# ISL6236A_DEMO.net
KiCad netlist of a schematic drawn in Altium Designer
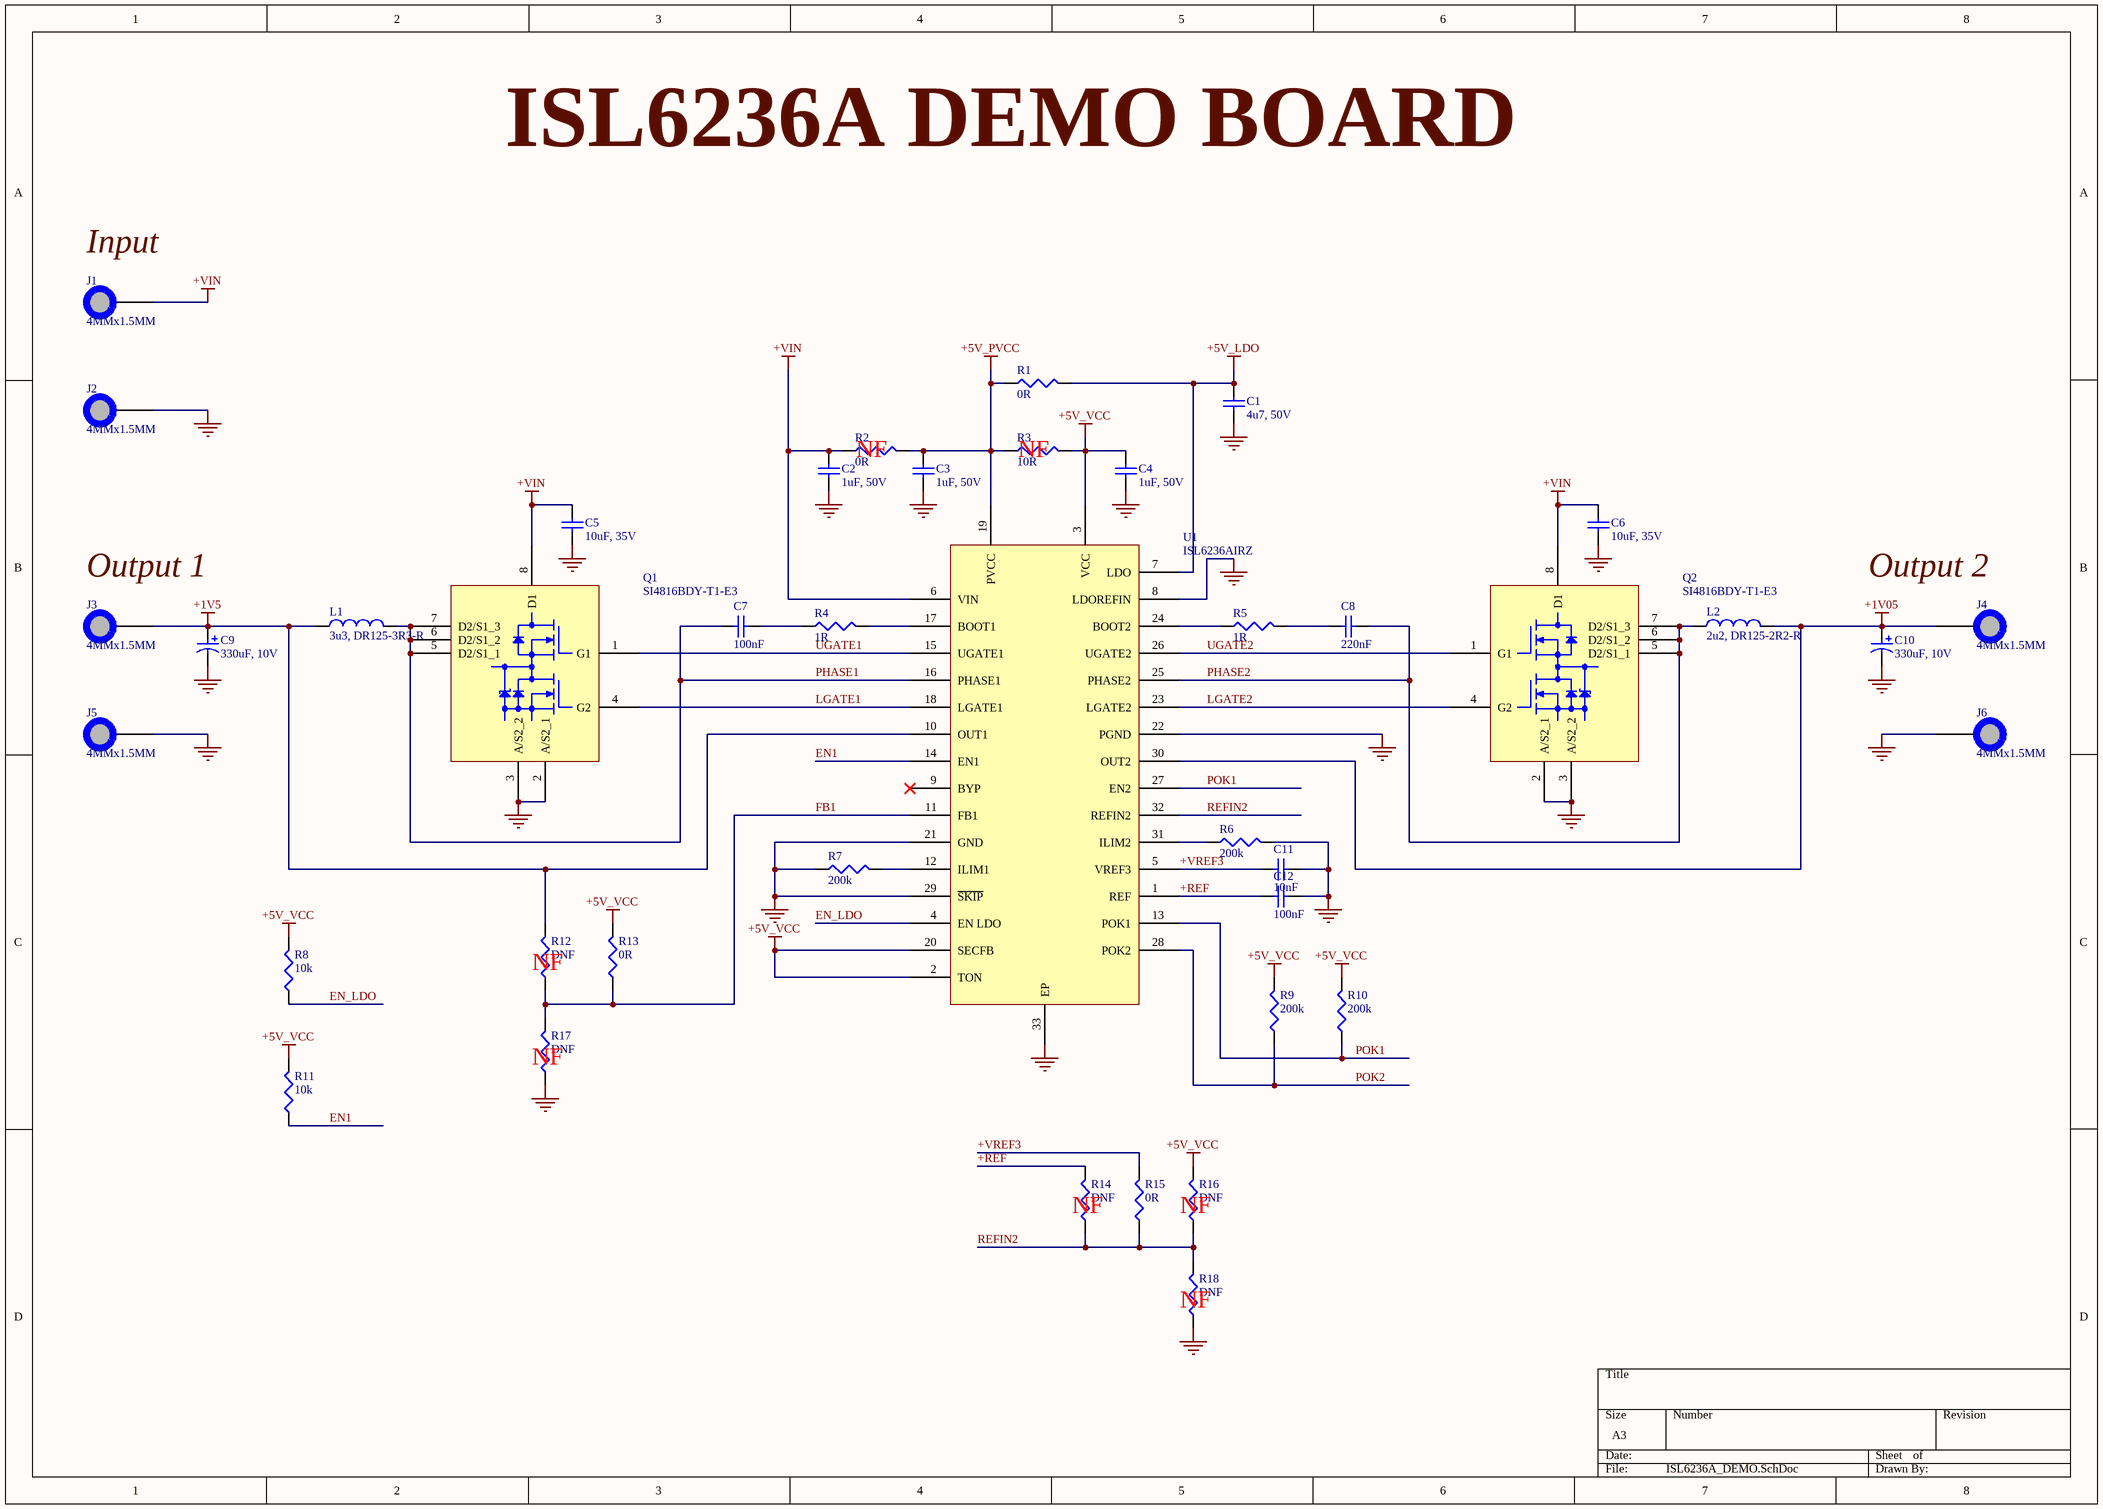
[diagram p0: ISL6236A_DEMO.SchDoc]

(export (version "E")
  (design (tool "Eeschema 10.0.6"))
  (components
    (comp (ref "C1")
      (value "4u7, 50V")
      (footprint "C1206")
      (description "CAP CER 4.7UF 50V X5R 1206")
      (fields
        (field (name "MANUFACTURER") "TDK")
        (field (name "MANUFACTURER PART NUMBER") "C3216X5R1H475K160AB")
      )
      (libsource (lib "ISL6236A_DEMO") (part "C3216X5R1H475K160AB"))
    )
    (comp (ref "C2")
      (value "1uF, 50V")
      (footprint "C0805")
      (description "Multilayer Ceramic Capacitors MLCC - SMD/SMT 1uF 50 Volts 10% X7R")
      (fields
        (field (name "MANUFACTURER") "KEMET")
        (field (name "MANUFACTURER PART NUMBER") "C0805C105K5RACTU")
      )
      (libsource (lib "ISL6236A_DEMO") (part "C0805C105K5RACTU"))
    )
    (comp (ref "C3")
      (value "1uF, 50V")
      (footprint "C0805")
      (description "Multilayer Ceramic Capacitors MLCC - SMD/SMT 1uF 50 Volts 10% X7R")
      (fields
        (field (name "MANUFACTURER") "KEMET")
        (field (name "MANUFACTURER PART NUMBER") "C0805C105K5RACTU")
      )
      (libsource (lib "ISL6236A_DEMO") (part "C0805C105K5RACTU"))
    )
    (comp (ref "C4")
      (value "1uF, 50V")
      (footprint "C0805")
      (description "Multilayer Ceramic Capacitors MLCC - SMD/SMT 1uF 50 Volts 10% X7R")
      (fields
        (field (name "MANUFACTURER") "KEMET")
        (field (name "MANUFACTURER PART NUMBER") "C0805C105K5RACTU")
      )
      (libsource (lib "ISL6236A_DEMO") (part "C0805C105K5RACTU"))
    )
    (comp (ref "C5")
      (value "10uF, 35V")
      (footprint "C1210")
      (description "1210 C 10uF Ceramic Multilayer Capacitor,  35 VDC,  +85degC,  X5R Dielec,  +/-10%")
      (fields
        (field (name "MANUFACTURER") "KEMET")
        (field (name "MANUFACTURER PART NUMBER") "C1210C106K6PACTU")
      )
      (libsource (lib "ISL6236A_DEMO") (part "C1210C106K6PACTU"))
    )
    (comp (ref "C6")
      (value "10uF, 35V")
      (footprint "C1210")
      (description "1210 C 10uF Ceramic Multilayer Capacitor,  35 VDC,  +85degC,  X5R Dielec,  +/-10%")
      (fields
        (field (name "MANUFACTURER") "KEMET")
        (field (name "MANUFACTURER PART NUMBER") "C1210C106K6PACTU")
      )
      (libsource (lib "ISL6236A_DEMO") (part "C1210C106K6PACTU"))
    )
    (comp (ref "C7")
      (value "100nF")
      (footprint "C0805")
      (description "Multilayer Ceramic Capacitors MLCC - SMD/SMT 50volts 0.1uF X7R 10%")
      (fields
        (field (name "MANUFACTURER") "KEMET")
        (field (name "MANUFACTURER PART NUMBER") "C0805C104K5RAC7800")
      )
      (libsource (lib "ISL6236A_DEMO") (part "C0805C104K5RAC7800"))
    )
    (comp (ref "C8")
      (value "220nF")
      (footprint "C0805")
      (description "CAP CER 0.22UF 50V X7R 0805")
      (fields
        (field (name "MANUFACTURER") "KEMET")
        (field (name "MANUFACTURER PART NUMBER") "C0805C224K5RACTU")
      )
      (libsource (lib "ISL6236A_DEMO") (part "C0805C224K5RACTU"))
    )
    (comp (ref "C9")
      (value "330uF, 10V")
      (footprint "7343-43")
      (description "Tantalum Capacitors - Polymer SMD 330uF 10volts 20%")
      (fields
        (field (name "MANUFACTURER") "KEMET")
        (field (name "MANUFACTURER PART NUMBER") "T530X337M010ATE004")
      )
      (libsource (lib "ISL6236A_DEMO") (part "T530X337M010ATE004"))
    )
    (comp (ref "C10")
      (value "330uF, 10V")
      (footprint "7343-43")
      (description "Tantalum Capacitors - Polymer SMD 330uF 10volts 20%")
      (fields
        (field (name "MANUFACTURER") "KEMET")
        (field (name "MANUFACTURER PART NUMBER") "T530X337M010ATE004")
      )
      (libsource (lib "ISL6236A_DEMO") (part "T530X337M010ATE004"))
    )
    (comp (ref "C11")
      (value "10nF")
      (footprint "C0805")
      (description "CAP CER 10000PF 50V X7R 0805")
      (fields
        (field (name "MANUFACTURER") "KEMET")
        (field (name "MANUFACTURER PART NUMBER") "C0805F103K5RACTU")
      )
      (libsource (lib "ISL6236A_DEMO") (part "C0805F103K5RACTU"))
    )
    (comp (ref "C12")
      (value "100nF")
      (footprint "C0805")
      (description "Multilayer Ceramic Capacitors MLCC - SMD/SMT 50volts 0.1uF X7R 10%")
      (fields
        (field (name "MANUFACTURER") "KEMET")
        (field (name "MANUFACTURER PART NUMBER") "C0805C104K5RAC7800")
      )
      (libsource (lib "ISL6236A_DEMO") (part "C0805C104K5RAC7800"))
    )
    (comp (ref "J1")
      (value "4MMx1.5MM")
      (footprint "PAD_WITH_HOLE_4MMx1MM5")
      (description "Pad with a hole 4mm x 1.5mm")
      (libsource (lib "ISL6236A_DEMO") (part "PAD_WITH_HOLE_4MMx1MM5"))
    )
    (comp (ref "J2")
      (value "4MMx1.5MM")
      (footprint "PAD_WITH_HOLE_4MMx1MM5")
      (description "Pad with a hole 4mm x 1.5mm")
      (libsource (lib "ISL6236A_DEMO") (part "PAD_WITH_HOLE_4MMx1MM5"))
    )
    (comp (ref "J3")
      (value "4MMx1.5MM")
      (footprint "PAD_WITH_HOLE_4MMx1MM5")
      (description "Pad with a hole 4mm x 1.5mm")
      (libsource (lib "ISL6236A_DEMO") (part "PAD_WITH_HOLE_4MMx1MM5"))
    )
    (comp (ref "J4")
      (value "4MMx1.5MM")
      (footprint "PAD_WITH_HOLE_4MMx1MM5")
      (description "Pad with a hole 4mm x 1.5mm")
      (libsource (lib "ISL6236A_DEMO") (part "PAD_WITH_HOLE_4MMx1MM5"))
    )
    (comp (ref "J5")
      (value "4MMx1.5MM")
      (footprint "PAD_WITH_HOLE_4MMx1MM5")
      (description "Pad with a hole 4mm x 1.5mm")
      (libsource (lib "ISL6236A_DEMO") (part "PAD_WITH_HOLE_4MMx1MM5"))
    )
    (comp (ref "J6")
      (value "4MMx1.5MM")
      (footprint "PAD_WITH_HOLE_4MMx1MM5")
      (description "Pad with a hole 4mm x 1.5mm")
      (libsource (lib "ISL6236A_DEMO") (part "PAD_WITH_HOLE_4MMx1MM5"))
    )
    (comp (ref "L1")
      (value "3u3, DR125-3R3-R")
      (footprint "DR125")
      (description "Inductor Power Shielded Drum Core 3.084uH/3.3uH 20% 100KHz Ferrite 9.26A 6.3mOhm DCR T/R")
      (fields
        (field (name "MANUFACTURER") "Eaton Cooper")
        (field (name "MANUFACTURER PART NUMBER") "DR125-3R3-R")
      )
      (libsource (lib "ISL6236A_DEMO") (part "DR125-3R3-R"))
    )
    (comp (ref "L2")
      (value "2u2, DR125-2R2-R")
      (footprint "DR125")
      (description "Fixed Inductors 2.2uH 15A 0.0045ohms")
      (fields
        (field (name "MANUFACTURER") "Eaton Cooper")
        (field (name "MANUFACTURER PART NUMBER") "DR125-2R2-R")
      )
      (libsource (lib "ISL6236A_DEMO") (part "DR125-2R2-R"))
    )
    (comp (ref "Q1")
      (value "SI4816BDY-T1-E3")
      (footprint "SO-8")
      (description "MOSFET 2N-CH 30V 5.8A 8-SOIC")
      (fields (field (name "MANUFACTURER") "Vishay Siliconix"))
      (libsource (lib "") (part "SI4816BDY-T1-E3_1"))
    )
    (comp (ref "Q2")
      (value "SI4816BDY-T1-E3")
      (footprint "SO-8")
      (description "MOSFET 2N-CH 30V 5.8A 8-SOIC")
      (fields (field (name "MANUFACTURER") "Vishay Siliconix"))
      (libsource (lib "ISL6236A_DEMO") (part "SI4816BDY-T1-E3"))
    )
    (comp (ref "R1")
      (value "0R")
      (footprint "R0805")
      (description "Thick Film Resistors - SMD 1/8W 0.0ohm 5%")
      (fields
        (field (name "MANUFACTURER") "Yageo")
        (field (name "MANUFACTURER PART NUMBER") "AC0805JR-070RL")
      )
      (libsource (lib "ISL6236A_DEMO") (part "AC0805JR-070RL"))
    )
    (comp (ref "R2")
      (value "0R")
      (footprint "R0805")
      (description "Thick Film Resistors - SMD 1/8W 0.0ohm 5%")
      (fields
        (field (name "MANUFACTURER") "Yageo")
        (field (name "MANUFACTURER PART NUMBER") "AC0805JR-070RL")
      )
      (libsource (lib "ISL6236A_DEMO") (part "AC0805JR-070RL"))
    )
    (comp (ref "R3")
      (value "10R")
      (footprint "R0805")
      (description "Thick Film Resistors - SMD 1/8W 10ohm 1%")
      (fields
        (field (name "MANUFACTURER") "Yageo")
        (field (name "MANUFACTURER PART NUMBER") "AC0805FR-0710RL")
      )
      (libsource (lib "ISL6236A_DEMO") (part "AC0805FR-0710RL"))
    )
    (comp (ref "R4")
      (value "1R")
      (footprint "R0805")
      (description "Thick Film Resistors - SMD 1/8W 1ohm 1% AEC-Q200")
      (fields
        (field (name "MANUFACTURER") "Yageo")
        (field (name "MANUFACTURER PART NUMBER") "AC0805FR-071RL")
      )
      (libsource (lib "ISL6236A_DEMO") (part "AC0805FR-071RL"))
    )
    (comp (ref "R5")
      (value "1R")
      (footprint "R0805")
      (description "Thick Film Resistors - SMD 1/8W 1ohm 1% AEC-Q200")
      (fields
        (field (name "MANUFACTURER") "Yageo")
        (field (name "MANUFACTURER PART NUMBER") "AC0805FR-071RL")
      )
      (libsource (lib "ISL6236A_DEMO") (part "AC0805FR-071RL"))
    )
    (comp (ref "R6")
      (value "200k")
      (footprint "R0805")
      (description "Thick Film Resistors - SMD 1/8W 200K ohm 1%")
      (fields
        (field (name "MANUFACTURER") "Yageo")
        (field (name "MANUFACTURER PART NUMBER") "AC0805FR-07200KL")
      )
      (libsource (lib "ISL6236A_DEMO") (part "AC0805FR-07200KL"))
    )
    (comp (ref "R7")
      (value "200k")
      (footprint "R0805")
      (description "Thick Film Resistors - SMD 1/8W 200K ohm 1%")
      (fields
        (field (name "MANUFACTURER") "Yageo")
        (field (name "MANUFACTURER PART NUMBER") "AC0805FR-07200KL")
      )
      (libsource (lib "ISL6236A_DEMO") (part "AC0805FR-07200KL"))
    )
    (comp (ref "R8")
      (value "10k")
      (footprint "R0805")
      (description "RES SMD 10K OHM 1% 1/8W 0805")
      (fields
        (field (name "MANUFACTURER") "Yageo")
        (field (name "MANUFACTURER PART NUMBER") "AC0805FR-0710KL")
      )
      (libsource (lib "ISL6236A_DEMO") (part "AC0805FR-0710KL"))
    )
    (comp (ref "R9")
      (value "200k")
      (footprint "R0805")
      (description "Thick Film Resistors - SMD 1/8W 200K ohm 1%")
      (fields
        (field (name "MANUFACTURER") "Yageo")
        (field (name "MANUFACTURER PART NUMBER") "AC0805FR-07200KL")
      )
      (libsource (lib "ISL6236A_DEMO") (part "AC0805FR-07200KL"))
    )
    (comp (ref "R10")
      (value "200k")
      (footprint "R0805")
      (description "Thick Film Resistors - SMD 1/8W 200K ohm 1%")
      (fields
        (field (name "MANUFACTURER") "Yageo")
        (field (name "MANUFACTURER PART NUMBER") "AC0805FR-07200KL")
      )
      (libsource (lib "ISL6236A_DEMO") (part "AC0805FR-07200KL"))
    )
    (comp (ref "R11")
      (value "10k")
      (footprint "R0805")
      (description "RES SMD 10K OHM 1% 1/8W 0805")
      (fields
        (field (name "MANUFACTURER") "Yageo")
        (field (name "MANUFACTURER PART NUMBER") "AC0805FR-0710KL")
      )
      (libsource (lib "ISL6236A_DEMO") (part "AC0805FR-0710KL"))
    )
    (comp (ref "R12") (value "DNF") (footprint "R0805") (libsource (lib "ISL6236A_DEMO") (part "RES")))
    (comp (ref "R13")
      (value "0R")
      (footprint "R0805")
      (description "Thick Film Resistors - SMD 1/8W 0.0ohm 5%")
      (fields
        (field (name "MANUFACTURER") "Yageo")
        (field (name "MANUFACTURER PART NUMBER") "AC0805JR-070RL")
      )
      (libsource (lib "ISL6236A_DEMO") (part "AC0805JR-070RL"))
    )
    (comp (ref "R14") (value "DNF") (footprint "R0805") (libsource (lib "ISL6236A_DEMO") (part "RES")))
    (comp (ref "R15")
      (value "0R")
      (footprint "R0805")
      (description "Thick Film Resistors - SMD 1/8W 0.0ohm 5%")
      (fields
        (field (name "MANUFACTURER") "Yageo")
        (field (name "MANUFACTURER PART NUMBER") "AC0805JR-070RL")
      )
      (libsource (lib "ISL6236A_DEMO") (part "AC0805JR-070RL"))
    )
    (comp (ref "R16") (value "DNF") (footprint "R0805") (libsource (lib "ISL6236A_DEMO") (part "RES")))
    (comp (ref "R17") (value "DNF") (footprint "R0805") (libsource (lib "ISL6236A_DEMO") (part "RES")))
    (comp (ref "R18") (value "DNF") (footprint "R0805") (libsource (lib "ISL6236A_DEMO") (part "RES")))
    (comp (ref "U1")
      (value "ISL6236AIRZ")
      (footprint "L32.5x5B")
      (description "IC MAIN PWR CTRLR QUAD 32-QFN")
      (fields (field (name "MANUFACTURER") "Intersil"))
      (libsource (lib "ISL6236A_DEMO") (part "ISL6236AIRZ"))
    )
  )
  (nets
    (net (code "1") (name "+1V05") (class "Default")
      (node (ref "C10") (pin "1") (pinfunction "1_1") (pintype "passive"))
      (node (ref "J4") (pin "1") (pinfunction "1_1") (pintype "passive"))
      (node (ref "L2") (pin "2") (pinfunction "2_2") (pintype "passive"))
      (node (ref "U1") (pin "30") (pinfunction "OUT2_30") (pintype "passive"))
    )
    (net (code "2") (name "+1V5") (class "Default")
      (node (ref "C9") (pin "1") (pinfunction "1_1") (pintype "passive"))
      (node (ref "J3") (pin "1") (pinfunction "1_1") (pintype "passive"))
      (node (ref "L1") (pin "1") (pinfunction "1_1") (pintype "passive"))
      (node (ref "R12") (pin "2") (pinfunction "2_2") (pintype "passive"))
      (node (ref "U1") (pin "10") (pinfunction "OUT1_10") (pintype "passive"))
    )
    (net (code "3") (name "+5V_LDO") (class "Default")
      (node (ref "C1") (pin "2") (pinfunction "2_2") (pintype "passive"))
      (node (ref "R1") (pin "2") (pinfunction "2_2") (pintype "passive"))
      (node (ref "U1") (pin "7") (pinfunction "LDO_7") (pintype "passive"))
    )
    (net (code "4") (name "+5V_PVCC") (class "Default")
      (node (ref "C3") (pin "2") (pinfunction "2_2") (pintype "passive"))
      (node (ref "R1") (pin "1") (pinfunction "1_1") (pintype "passive"))
      (node (ref "R2") (pin "2") (pinfunction "2_2") (pintype "passive"))
      (node (ref "R3") (pin "1") (pinfunction "1_1") (pintype "passive"))
      (node (ref "U1") (pin "19") (pinfunction "PVCC_19") (pintype "passive"))
    )
    (net (code "5") (name "+5V_VCC") (class "Default")
      (node (ref "C4") (pin "2") (pinfunction "2_2") (pintype "passive"))
      (node (ref "R10") (pin "2") (pinfunction "2_2") (pintype "passive"))
      (node (ref "R11") (pin "2") (pinfunction "2_2") (pintype "passive"))
      (node (ref "R13") (pin "2") (pinfunction "2_2") (pintype "passive"))
      (node (ref "R16") (pin "2") (pinfunction "2_2") (pintype "passive"))
      (node (ref "R3") (pin "2") (pinfunction "2_2") (pintype "passive"))
      (node (ref "R8") (pin "2") (pinfunction "2_2") (pintype "passive"))
      (node (ref "R9") (pin "2") (pinfunction "2_2") (pintype "passive"))
      (node (ref "U1") (pin "2") (pinfunction "TON_2") (pintype "passive"))
      (node (ref "U1") (pin "20") (pinfunction "SECFB_20") (pintype "passive"))
      (node (ref "U1") (pin "3") (pinfunction "VCC_3") (pintype "passive"))
    )
    (net (code "6") (name "+VIN") (class "Default")
      (node (ref "C2") (pin "2") (pinfunction "2_2") (pintype "passive"))
      (node (ref "C5") (pin "2") (pinfunction "2_2") (pintype "passive"))
      (node (ref "C6") (pin "2") (pinfunction "2_2") (pintype "passive"))
      (node (ref "J1") (pin "1") (pinfunction "1_1") (pintype "passive"))
      (node (ref "Q1") (pin "8") (pinfunction "D1_8") (pintype "passive"))
      (node (ref "Q2") (pin "8") (pinfunction "D1_8") (pintype "passive"))
      (node (ref "R2") (pin "1") (pinfunction "1_1") (pintype "passive"))
      (node (ref "U1") (pin "6") (pinfunction "VIN_6") (pintype "passive"))
    )
    (net (code "7") (name "/+REF") (class "Default")
      (node (ref "C12") (pin "1") (pinfunction "1_1") (pintype "passive"))
      (node (ref "R14") (pin "2") (pinfunction "2_2") (pintype "passive"))
      (node (ref "U1") (pin "1") (pinfunction "REF_1") (pintype "passive"))
    )
    (net (code "8") (name "/+VREF3") (class "Default")
      (node (ref "C11") (pin "1") (pinfunction "1_1") (pintype "passive"))
      (node (ref "R15") (pin "2") (pinfunction "2_2") (pintype "passive"))
      (node (ref "U1") (pin "5") (pinfunction "VREF3_5") (pintype "passive"))
    )
    (net (code "9") (name "/EN1") (class "Default")
      (node (ref "R11") (pin "1") (pinfunction "1_1") (pintype "passive"))
      (node (ref "U1") (pin "14") (pinfunction "EN1_14") (pintype "passive"))
    )
    (net (code "10") (name "/EN_LDO") (class "Default")
      (node (ref "R8") (pin "1") (pinfunction "1_1") (pintype "passive"))
      (node (ref "U1") (pin "4") (pinfunction "EN_LDO_4") (pintype "passive"))
    )
    (net (code "11") (name "/FB1") (class "Default")
      (node (ref "R12") (pin "1") (pinfunction "1_1") (pintype "passive"))
      (node (ref "R13") (pin "1") (pinfunction "1_1") (pintype "passive"))
      (node (ref "R17") (pin "2") (pinfunction "2_2") (pintype "passive"))
      (node (ref "U1") (pin "11") (pinfunction "FB1_11") (pintype "passive"))
    )
    (net (code "12") (name "/LGATE1") (class "Default")
      (node (ref "Q1") (pin "4") (pinfunction "G2_4") (pintype "passive"))
      (node (ref "U1") (pin "18") (pinfunction "LGATE1_18") (pintype "passive"))
    )
    (net (code "13") (name "/LGATE2") (class "Default")
      (node (ref "Q2") (pin "4") (pinfunction "G2_4") (pintype "passive"))
      (node (ref "U1") (pin "23") (pinfunction "LGATE2_23") (pintype "passive"))
    )
    (net (code "14") (name "/PHASE1") (class "Default")
      (node (ref "C7") (pin "1") (pinfunction "1_1") (pintype "passive"))
      (node (ref "L1") (pin "2") (pinfunction "2_2") (pintype "passive"))
      (node (ref "Q1") (pin "5") (pinfunction "D2/S1_1_5") (pintype "passive"))
      (node (ref "Q1") (pin "6") (pinfunction "D2/S1_2_6") (pintype "passive"))
      (node (ref "Q1") (pin "7") (pinfunction "D2/S1_3_7") (pintype "passive"))
      (node (ref "U1") (pin "16") (pinfunction "PHASE1_16") (pintype "passive"))
    )
    (net (code "15") (name "/PHASE2") (class "Default")
      (node (ref "C8") (pin "2") (pinfunction "2_2") (pintype "passive"))
      (node (ref "L2") (pin "1") (pinfunction "1_1") (pintype "passive"))
      (node (ref "Q2") (pin "5") (pinfunction "D2/S1_1_5") (pintype "passive"))
      (node (ref "Q2") (pin "6") (pinfunction "D2/S1_2_6") (pintype "passive"))
      (node (ref "Q2") (pin "7") (pinfunction "D2/S1_3_7") (pintype "passive"))
      (node (ref "U1") (pin "25") (pinfunction "PHASE2_25") (pintype "passive"))
    )
    (net (code "16") (name "/POK1") (class "Default")
      (node (ref "R10") (pin "1") (pinfunction "1_1") (pintype "passive"))
      (node (ref "U1") (pin "13") (pinfunction "POK1_13") (pintype "passive"))
      (node (ref "U1") (pin "27") (pinfunction "EN2_27") (pintype "passive"))
    )
    (net (code "17") (name "/POK2") (class "Default")
      (node (ref "R9") (pin "1") (pinfunction "1_1") (pintype "passive"))
      (node (ref "U1") (pin "28") (pinfunction "POK2_28") (pintype "passive"))
    )
    (net (code "18") (name "/REFIN2") (class "Default")
      (node (ref "R14") (pin "1") (pinfunction "1_1") (pintype "passive"))
      (node (ref "R15") (pin "1") (pinfunction "1_1") (pintype "passive"))
      (node (ref "R16") (pin "1") (pinfunction "1_1") (pintype "passive"))
      (node (ref "R18") (pin "2") (pinfunction "2_2") (pintype "passive"))
      (node (ref "U1") (pin "32") (pinfunction "REFIN2_32") (pintype "passive"))
    )
    (net (code "19") (name "/UGATE1") (class "Default")
      (node (ref "Q1") (pin "1") (pinfunction "G1_1") (pintype "passive"))
      (node (ref "U1") (pin "15") (pinfunction "UGATE1_15") (pintype "passive"))
    )
    (net (code "20") (name "/UGATE2") (class "Default")
      (node (ref "Q2") (pin "1") (pinfunction "G1_1") (pintype "passive"))
      (node (ref "U1") (pin "26") (pinfunction "UGATE2_26") (pintype "passive"))
    )
    (net (code "21") (name "GND") (class "Default")
      (node (ref "C1") (pin "1") (pinfunction "1_1") (pintype "passive"))
      (node (ref "C10") (pin "2") (pinfunction "2_2") (pintype "passive"))
      (node (ref "C11") (pin "2") (pinfunction "2_2") (pintype "passive"))
      (node (ref "C12") (pin "2") (pinfunction "2_2") (pintype "passive"))
      (node (ref "C2") (pin "1") (pinfunction "1_1") (pintype "passive"))
      (node (ref "C3") (pin "1") (pinfunction "1_1") (pintype "passive"))
      (node (ref "C4") (pin "1") (pinfunction "1_1") (pintype "passive"))
      (node (ref "C5") (pin "1") (pinfunction "1_1") (pintype "passive"))
      (node (ref "C6") (pin "1") (pinfunction "1_1") (pintype "passive"))
      (node (ref "C9") (pin "2") (pinfunction "2_2") (pintype "passive"))
      (node (ref "J2") (pin "1") (pinfunction "1_1") (pintype "passive"))
      (node (ref "J5") (pin "1") (pinfunction "1_1") (pintype "passive"))
      (node (ref "J6") (pin "1") (pinfunction "1_1") (pintype "passive"))
      (node (ref "Q1") (pin "2") (pinfunction "A/S2_1_2") (pintype "passive"))
      (node (ref "Q1") (pin "3") (pinfunction "A/S2_2_3") (pintype "passive"))
      (node (ref "Q2") (pin "2") (pinfunction "A/S2_1_2") (pintype "passive"))
      (node (ref "Q2") (pin "3") (pinfunction "A/S2_2_3") (pintype "passive"))
      (node (ref "R17") (pin "1") (pinfunction "1_1") (pintype "passive"))
      (node (ref "R18") (pin "1") (pinfunction "1_1") (pintype "passive"))
      (node (ref "R6") (pin "2") (pinfunction "2_2") (pintype "passive"))
      (node (ref "R7") (pin "1") (pinfunction "1_1") (pintype "passive"))
      (node (ref "U1") (pin "21") (pinfunction "GND_21") (pintype "passive"))
      (node (ref "U1") (pin "22") (pinfunction "PGND_22") (pintype "passive"))
      (node (ref "U1") (pin "29") (pinfunction "~{SKIP}_29") (pintype "passive"))
      (node (ref "U1") (pin "33") (pinfunction "EP_33") (pintype "passive"))
      (node (ref "U1") (pin "8") (pinfunction "LDOREFIN_8") (pintype "passive"))
    )
    (net (code "22") (name "Net-(C7-Pad2)") (class "Default")
      (node (ref "C7") (pin "2") (pinfunction "2_2") (pintype "passive"))
      (node (ref "R4") (pin "1") (pinfunction "1_1") (pintype "passive"))
    )
    (net (code "23") (name "Net-(C8-Pad1)") (class "Default")
      (node (ref "C8") (pin "1") (pinfunction "1_1") (pintype "passive"))
      (node (ref "R5") (pin "2") (pinfunction "2_2") (pintype "passive"))
    )
    (net (code "24") (name "Net-(U1-BOOT1)") (class "Default")
      (node (ref "R4") (pin "2") (pinfunction "2_2") (pintype "passive"))
      (node (ref "U1") (pin "17") (pinfunction "BOOT1_17") (pintype "passive"))
    )
    (net (code "25") (name "Net-(U1-BOOT2)") (class "Default")
      (node (ref "R5") (pin "1") (pinfunction "1_1") (pintype "passive"))
      (node (ref "U1") (pin "24") (pinfunction "BOOT2_24") (pintype "passive"))
    )
    (net (code "26") (name "Net-(U1-ILIM1)") (class "Default")
      (node (ref "R7") (pin "2") (pinfunction "2_2") (pintype "passive"))
      (node (ref "U1") (pin "12") (pinfunction "ILIM1_12") (pintype "passive"))
    )
    (net (code "27") (name "Net-(U1-ILIM2)") (class "Default")
      (node (ref "R6") (pin "1") (pinfunction "1_1") (pintype "passive"))
      (node (ref "U1") (pin "31") (pinfunction "ILIM2_31") (pintype "passive"))
    )
    (net (code "28") (name "unconnected-(U1-BYP-Pad9)") (class "Default")
      (node (ref "U1") (pin "9") (pinfunction "BYP_9") (pintype "passive+no_connect"))
    )
  )
)
